# 05-GPS_IMU_SENSORS.net
KiCad netlist of a schematic drawn in Altium Designer
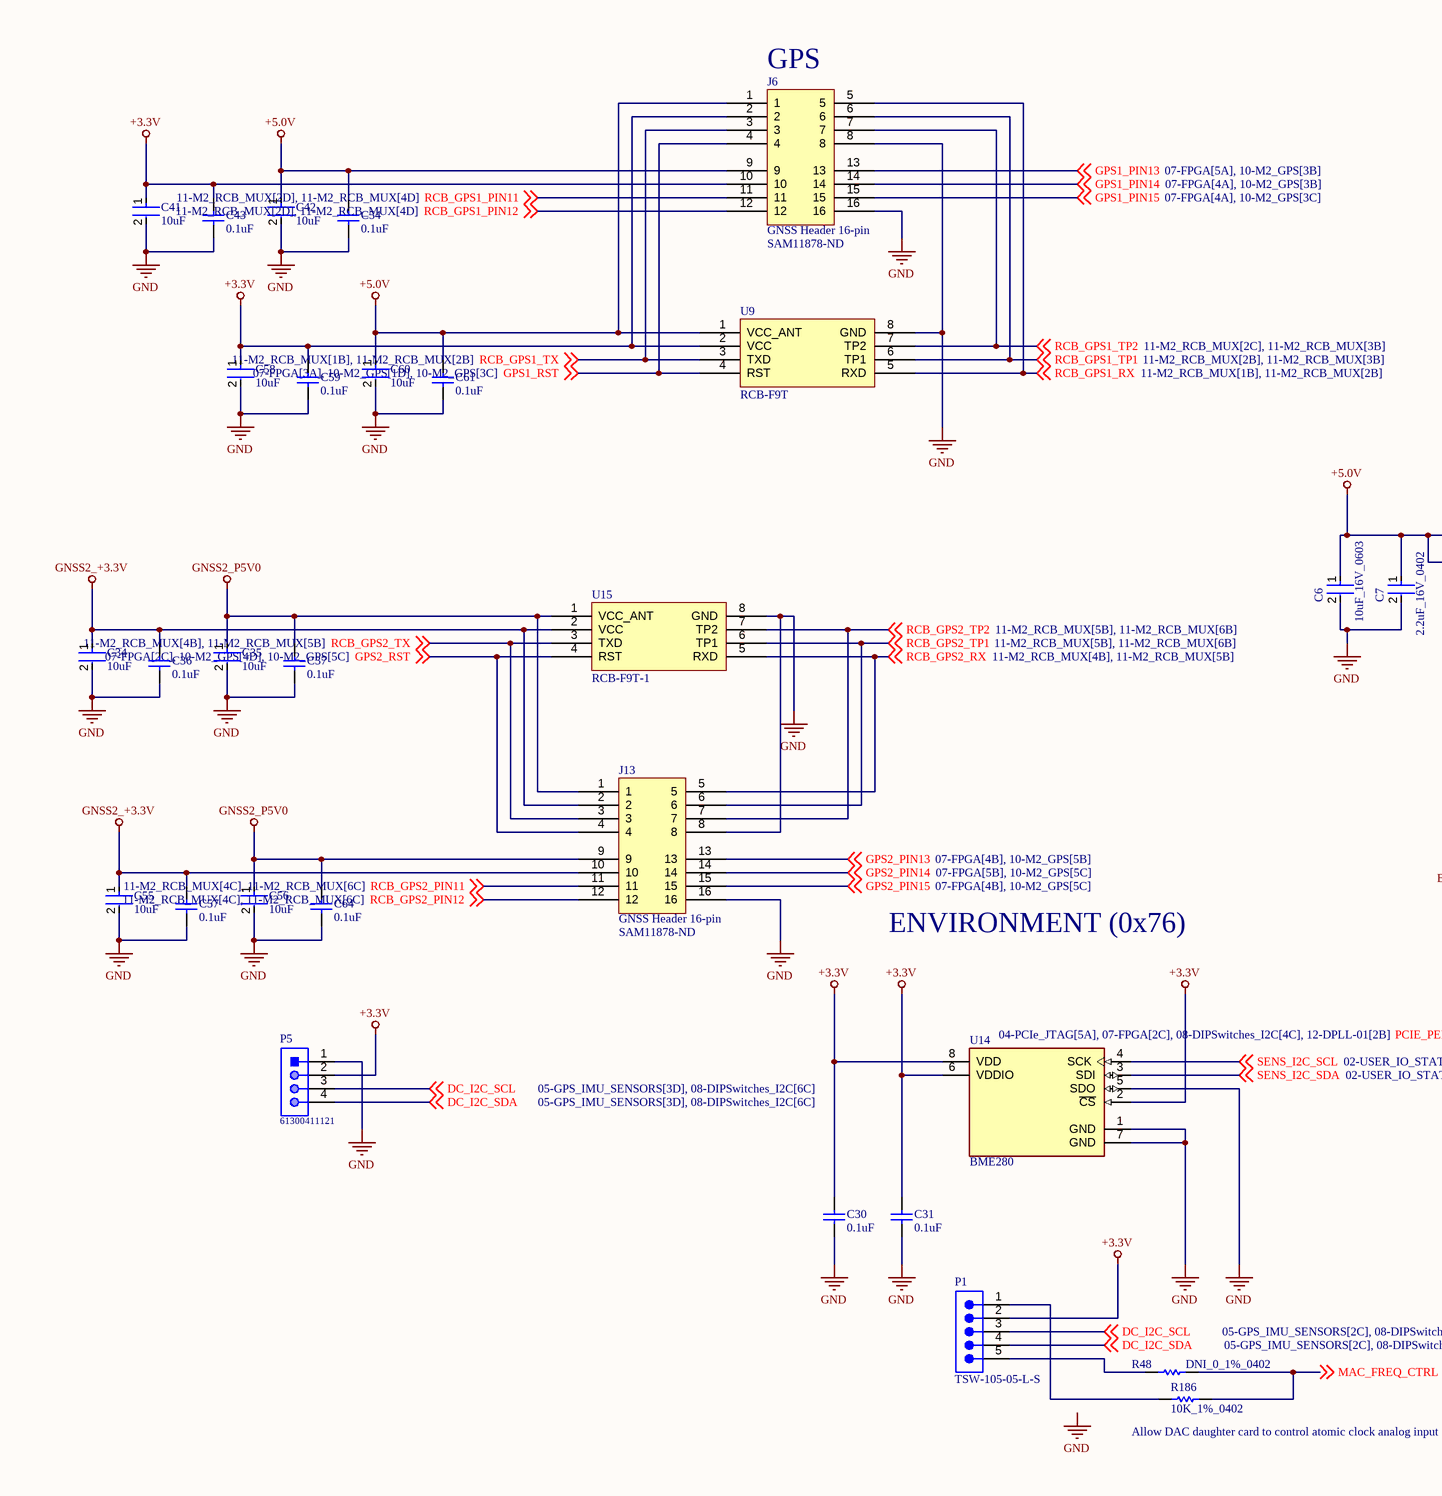
[diagram p0: 05-GPS_IMU_SENSORS.SchDoc, left]
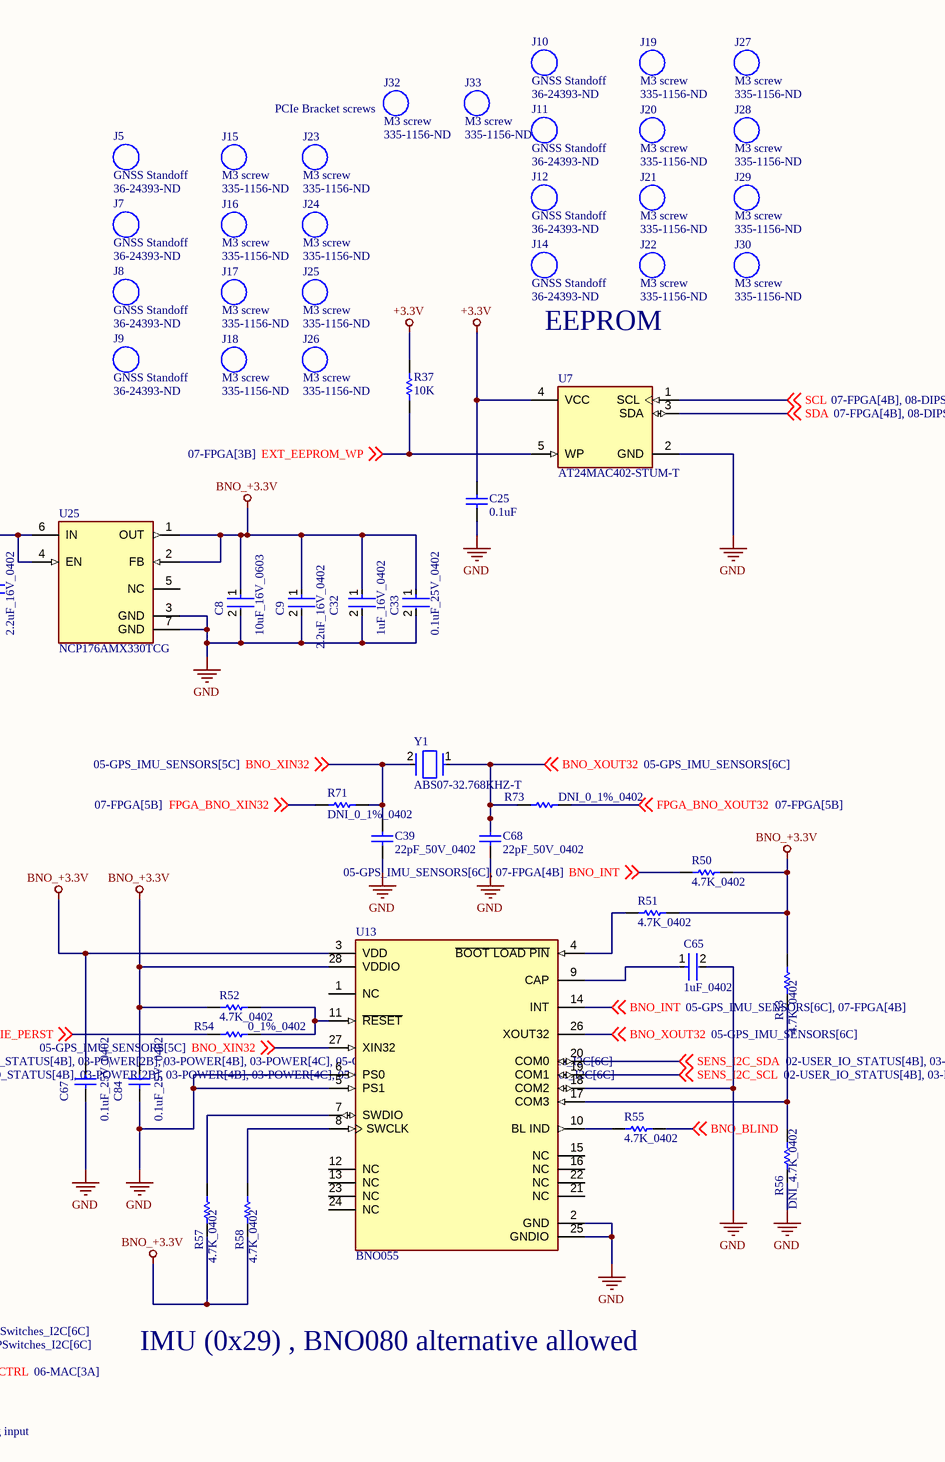
[diagram p1: 05-GPS_IMU_SENSORS.SchDoc, right]

(export (version "E")
  (design (tool "Eeschema 10.0.6"))
  (components
    (comp (ref "C6")
      (value "10uF_16V_0603")
      (footprint "FP-0603-L_1_6_0_2-W_0_8_0-MFG")
      (description "Multilayer Ceramic Capacitor 10uF 16V X5R 20% SMD 0603 T/R")
      (fields (field (name "TOLERANCE") "20%"))
      (libsource (lib "Altium Content Vault") (part "b4654b650e69147ec39a6b967a45e02"))
    )
    (comp (ref "C7")
      (value "2.2uF_16V_0402")
      (footprint "FP-C1005-050-0_05-IPC_A")
      (description "Multilayer Ceramic Capacitors 2.2μF ±10% 16V X5R SMD 0402")
      (fields (field (name "TOLERANCE") "10%"))
      (libsource (lib "Altium Content Vault") (part "b4654b650e69147ec39a6b967a45e02"))
    )
    (comp (ref "C8")
      (value "10uF_16V_0603")
      (footprint "FP-0603-L_1_6_0_2-W_0_8_0-MFG")
      (description "Multilayer Ceramic Capacitor 10uF 16V X5R 20% SMD 0603 T/R")
      (fields (field (name "TOLERANCE") "20%"))
      (libsource (lib "Altium Content Vault") (part "b4654b650e69147ec39a6b967a45e02"))
    )
    (comp (ref "C9")
      (value "2.2uF_16V_0402")
      (footprint "FP-C1005-050-0_05-IPC_A")
      (description "Multilayer Ceramic Capacitors 2.2μF ±10% 16V X5R SMD 0402")
      (fields (field (name "TOLERANCE") "10%"))
      (libsource (lib "Altium Content Vault") (part "b4654b650e69147ec39a6b967a45e02"))
    )
    (comp (ref "C25")
      (value "0.1uF")
      (footprint "CAPC1608X87X45ML20T05")
      (description "C0603X104K5RACAUTO")
      (fields (field (name "MANUFACTURER") "Kemet"))
      (libsource (lib "Altium Content Vault") (part "CAP"))
    )
    (comp (ref "C30")
      (value "0.1uF")
      (footprint "CAPC1608X87X45ML20T05")
      (description "C0603X104K5RACAUTO")
      (fields (field (name "MANUFACTURER") "Kemet"))
      (libsource (lib "Altium Content Vault") (part "CAP"))
    )
    (comp (ref "C31")
      (value "0.1uF")
      (footprint "CAPC1608X87X45ML20T05")
      (description "C0603X104K5RACAUTO")
      (fields (field (name "MANUFACTURER") "Kemet"))
      (libsource (lib "Altium Content Vault") (part "CAP"))
    )
    (comp (ref "C32")
      (value "1uF_16V_0402")
      (footprint "FP-0402-L_1_0_0_05-W_0_5-IPC_A")
      (description "None")
      (fields (field (name "TOLERANCE") "10%"))
      (libsource (lib "Altium Content Vault") (part "b4654b650e69147ec39a6b967a45e02"))
    )
    (comp (ref "C33")
      (value "0.1uF_25V_0402")
      (footprint "FP-0402-L_1_0_1-W_0_5_0_1-IPC_C")
      (description "General Purpose Ceramic Capacitor, 0402, 100nF, 10%, X7R, 15%, 25V")
      (fields (field (name "VOLTAGE") "25V") (field (name "TOLERANCE") "10%"))
      (libsource (lib "Altium Content Vault") (part "b4654b650e69147ec39a6b967a45e02"))
    )
    (comp (ref "C34")
      (value "10uF")
      (footprint "FP-MK212BG-MFG")
      (description "None")
      (fields (field (name "TOLERANCE") "10%") (field (name "VOLTAGE") "16V"))
      (libsource (lib "Altium Content Vault") (part "b4654b650e69147ec39a6b967a45e02"))
    )
    (comp (ref "C35")
      (value "10uF")
      (footprint "FP-MK212BG-MFG")
      (description "None")
      (fields (field (name "TOLERANCE") "10%") (field (name "VOLTAGE") "16V"))
      (libsource (lib "Altium Content Vault") (part "b4654b650e69147ec39a6b967a45e02"))
    )
    (comp (ref "C36")
      (value "0.1uF")
      (footprint "CAPC1608X87X45ML20T05")
      (description "C0603X104K5RACAUTO")
      (fields (field (name "MANUFACTURER") "Kemet"))
      (libsource (lib "Altium Content Vault") (part "CAP"))
    )
    (comp (ref "C37")
      (value "0.1uF")
      (footprint "CAPC1608X87X45ML20T05")
      (description "C0603X104K5RACAUTO")
      (fields (field (name "MANUFACTURER") "Kemet"))
      (libsource (lib "Altium Content Vault") (part "CAP"))
    )
    (comp (ref "C39")
      (value "22pF_50V_0402")
      (footprint "CAPC1005X55X25ML05T05")
      (description "Chip Capacitor, 22 pF, +/- 5%, 50 V, -55 to 125 degC, 0402 (1005 Metric), RoHS, Tape and Reel")
      (fields (field (name "MANUFACTURER") "Yageo") (field (name "TOLERANCE") "5%"))
      (libsource (lib "Altium Content Vault") (part "CAP-NP-2"))
    )
    (comp (ref "C41")
      (value "10uF")
      (footprint "FP-MK212BG-MFG")
      (description "None")
      (fields (field (name "TOLERANCE") "10%") (field (name "VOLTAGE") "16V"))
      (libsource (lib "Altium Content Vault") (part "b4654b650e69147ec39a6b967a45e02"))
    )
    (comp (ref "C42")
      (value "10uF")
      (footprint "FP-MK212BG-MFG")
      (description "None")
      (fields (field (name "TOLERANCE") "10%") (field (name "VOLTAGE") "16V"))
      (libsource (lib "Altium Content Vault") (part "b4654b650e69147ec39a6b967a45e02"))
    )
    (comp (ref "C43")
      (value "0.1uF")
      (footprint "CAPC1608X87X45ML20T05")
      (description "C0603X104K5RACAUTO")
      (fields (field (name "MANUFACTURER") "Kemet"))
      (libsource (lib "Altium Content Vault") (part "CAP"))
    )
    (comp (ref "C54")
      (value "0.1uF")
      (footprint "CAPC1608X87X45ML20T05")
      (description "C0603X104K5RACAUTO")
      (fields (field (name "MANUFACTURER") "Kemet"))
      (libsource (lib "Altium Content Vault") (part "CAP"))
    )
    (comp (ref "C55")
      (value "10uF")
      (footprint "FP-MK212BG-MFG")
      (description "None")
      (fields (field (name "TOLERANCE") "10%") (field (name "VOLTAGE") "16V"))
      (libsource (lib "Altium Content Vault") (part "b4654b650e69147ec39a6b967a45e02"))
    )
    (comp (ref "C56")
      (value "10uF")
      (footprint "FP-MK212BG-MFG")
      (description "None")
      (fields (field (name "TOLERANCE") "10%") (field (name "VOLTAGE") "16V"))
      (libsource (lib "Altium Content Vault") (part "b4654b650e69147ec39a6b967a45e02"))
    )
    (comp (ref "C57")
      (value "0.1uF")
      (footprint "CAPC1608X87X45ML20T05")
      (description "C0603X104K5RACAUTO")
      (fields (field (name "MANUFACTURER") "Kemet"))
      (libsource (lib "Altium Content Vault") (part "CAP"))
    )
    (comp (ref "C58")
      (value "10uF")
      (footprint "FP-MK212BG-MFG")
      (description "None")
      (fields (field (name "TOLERANCE") "10%") (field (name "VOLTAGE") "16V"))
      (libsource (lib "Altium Content Vault") (part "b4654b650e69147ec39a6b967a45e02"))
    )
    (comp (ref "C59")
      (value "0.1uF")
      (footprint "CAPC1608X87X45ML20T05")
      (description "C0603X104K5RACAUTO")
      (fields (field (name "MANUFACTURER") "Kemet"))
      (libsource (lib "Altium Content Vault") (part "CAP"))
    )
    (comp (ref "C60")
      (value "10uF")
      (footprint "FP-MK212BG-MFG")
      (description "None")
      (fields (field (name "TOLERANCE") "10%") (field (name "VOLTAGE") "16V"))
      (libsource (lib "Altium Content Vault") (part "b4654b650e69147ec39a6b967a45e02"))
    )
    (comp (ref "C61")
      (value "0.1uF")
      (footprint "CAPC1608X87X45ML20T05")
      (description "C0603X104K5RACAUTO")
      (fields (field (name "MANUFACTURER") "Kemet"))
      (libsource (lib "Altium Content Vault") (part "CAP"))
    )
    (comp (ref "C64")
      (value "0.1uF")
      (footprint "CAPC1608X87X45ML20T05")
      (description "C0603X104K5RACAUTO")
      (fields (field (name "MANUFACTURER") "Kemet"))
      (libsource (lib "Altium Content Vault") (part "CAP"))
    )
    (comp (ref "C65")
      (value "1uF_0402")
      (footprint "FP-0402-L_1_0_0_05-W_0_5-IPC_C")
      (description "None")
      (fields (field (name "TOLERANCE") "20%") (field (name "VOLTAGE") "16V"))
      (libsource (lib "Altium Content Vault") (part "b4654b650e69147ec39a6b967a45e02"))
    )
    (comp (ref "C67")
      (value "0.1uF_25V_0402")
      (footprint "CAPC1005X56X25NL10T15")
      (fields
        (field (name "PART NUMBER") "04023D104KAT2A")
        (field (name "MANUFACTURER") "AVX Interconnect / Elco")
      )
      (libsource (lib "Altium Content Vault") (part "CAP"))
    )
    (comp (ref "C68")
      (value "22pF_50V_0402")
      (footprint "CAPC1005X55X25ML05T05")
      (description "Chip Capacitor, 22 pF, +/- 5%, 50 V, -55 to 125 degC, 0402 (1005 Metric), RoHS, Tape and Reel")
      (fields (field (name "MANUFACTURER") "Yageo") (field (name "TOLERANCE") "5%"))
      (libsource (lib "Altium Content Vault") (part "CAP-NP-2"))
    )
    (comp (ref "C84")
      (value "0.1uF_25V_0402")
      (footprint "CAPC1005X56X25NL10T15")
      (fields
        (field (name "PART NUMBER") "04023D104KAT2A")
        (field (name "MANUFACTURER") "AVX Interconnect / Elco")
      )
      (libsource (lib "Altium Content Vault") (part "CAP"))
    )
    (comp (ref "J5")
      (value "GNSS Standoff")
      (fields (field (name "SUPPLIER PART NUMBER 1") "36-24393-ND"))
      (libsource (lib "FPGA_CONN") (part "GNSS Standoff"))
    )
    (comp (ref "J6")
      (value "GNSS Header 16-pin")
      (footprint "GNSS Header 16-pin")
      (fields (field (name "SUPPLIER PART NUMBER 1") "SAM11878-ND"))
      (libsource (lib "FPGA_CONN") (part "GNSS Header 16-pin"))
    )
    (comp (ref "J7")
      (value "GNSS Standoff")
      (fields (field (name "SUPPLIER PART NUMBER 1") "36-24393-ND"))
      (libsource (lib "FPGA_CONN") (part "GNSS Standoff"))
    )
    (comp (ref "J8")
      (value "GNSS Standoff")
      (fields (field (name "SUPPLIER PART NUMBER 1") "36-24393-ND"))
      (libsource (lib "FPGA_CONN") (part "GNSS Standoff"))
    )
    (comp (ref "J9")
      (value "GNSS Standoff")
      (fields (field (name "SUPPLIER PART NUMBER 1") "36-24393-ND"))
      (libsource (lib "FPGA_CONN") (part "GNSS Standoff"))
    )
    (comp (ref "J10")
      (value "GNSS Standoff")
      (fields (field (name "SUPPLIER PART NUMBER 1") "36-24393-ND"))
      (libsource (lib "FPGA_CONN") (part "GNSS Standoff"))
    )
    (comp (ref "J11")
      (value "GNSS Standoff")
      (fields (field (name "SUPPLIER PART NUMBER 1") "36-24393-ND"))
      (libsource (lib "FPGA_CONN") (part "GNSS Standoff"))
    )
    (comp (ref "J12")
      (value "GNSS Standoff")
      (fields (field (name "SUPPLIER PART NUMBER 1") "36-24393-ND"))
      (libsource (lib "FPGA_CONN") (part "GNSS Standoff"))
    )
    (comp (ref "J13")
      (value "GNSS Header 16-pin")
      (footprint "GNSS Header 16-pin")
      (fields (field (name "SUPPLIER PART NUMBER 1") "SAM11878-ND"))
      (libsource (lib "FPGA_CONN") (part "GNSS Header 16-pin"))
    )
    (comp (ref "J14")
      (value "GNSS Standoff")
      (fields (field (name "SUPPLIER PART NUMBER 1") "36-24393-ND"))
      (libsource (lib "FPGA_CONN") (part "GNSS Standoff"))
    )
    (comp (ref "J15")
      (value "M3 screw")
      (fields (field (name "SUPPLIER PART NUMBER 1") "335-1156-ND"))
      (libsource (lib "FPGA_CONN") (part "M3 screw"))
    )
    (comp (ref "J16")
      (value "M3 screw")
      (fields (field (name "SUPPLIER PART NUMBER 1") "335-1156-ND"))
      (libsource (lib "FPGA_CONN") (part "M3 screw"))
    )
    (comp (ref "J17")
      (value "M3 screw")
      (fields (field (name "SUPPLIER PART NUMBER 1") "335-1156-ND"))
      (libsource (lib "FPGA_CONN") (part "M3 screw"))
    )
    (comp (ref "J18")
      (value "M3 screw")
      (fields (field (name "SUPPLIER PART NUMBER 1") "335-1156-ND"))
      (libsource (lib "FPGA_CONN") (part "M3 screw"))
    )
    (comp (ref "J19")
      (value "M3 screw")
      (fields (field (name "SUPPLIER PART NUMBER 1") "335-1156-ND"))
      (libsource (lib "FPGA_CONN") (part "M3 screw"))
    )
    (comp (ref "J20")
      (value "M3 screw")
      (fields (field (name "SUPPLIER PART NUMBER 1") "335-1156-ND"))
      (libsource (lib "FPGA_CONN") (part "M3 screw"))
    )
    (comp (ref "J21")
      (value "M3 screw")
      (fields (field (name "SUPPLIER PART NUMBER 1") "335-1156-ND"))
      (libsource (lib "FPGA_CONN") (part "M3 screw"))
    )
    (comp (ref "J22")
      (value "M3 screw")
      (fields (field (name "SUPPLIER PART NUMBER 1") "335-1156-ND"))
      (libsource (lib "FPGA_CONN") (part "M3 screw"))
    )
    (comp (ref "J23")
      (value "M3 screw")
      (fields (field (name "SUPPLIER PART NUMBER 1") "335-1156-ND"))
      (libsource (lib "FPGA_CONN") (part "M3 screw"))
    )
    (comp (ref "J24")
      (value "M3 screw")
      (fields (field (name "SUPPLIER PART NUMBER 1") "335-1156-ND"))
      (libsource (lib "FPGA_CONN") (part "M3 screw"))
    )
    (comp (ref "J25")
      (value "M3 screw")
      (fields (field (name "SUPPLIER PART NUMBER 1") "335-1156-ND"))
      (libsource (lib "FPGA_CONN") (part "M3 screw"))
    )
    (comp (ref "J26")
      (value "M3 screw")
      (fields (field (name "SUPPLIER PART NUMBER 1") "335-1156-ND"))
      (libsource (lib "FPGA_CONN") (part "M3 screw"))
    )
    (comp (ref "J27")
      (value "M3 screw")
      (fields (field (name "SUPPLIER PART NUMBER 1") "335-1156-ND"))
      (libsource (lib "FPGA_CONN") (part "M3 screw"))
    )
    (comp (ref "J28")
      (value "M3 screw")
      (fields (field (name "SUPPLIER PART NUMBER 1") "335-1156-ND"))
      (libsource (lib "FPGA_CONN") (part "M3 screw"))
    )
    (comp (ref "J29")
      (value "M3 screw")
      (fields (field (name "SUPPLIER PART NUMBER 1") "335-1156-ND"))
      (libsource (lib "FPGA_CONN") (part "M3 screw"))
    )
    (comp (ref "J30")
      (value "M3 screw")
      (fields (field (name "SUPPLIER PART NUMBER 1") "335-1156-ND"))
      (libsource (lib "FPGA_CONN") (part "M3 screw"))
    )
    (comp (ref "J32")
      (value "M3 screw")
      (fields (field (name "SUPPLIER PART NUMBER 1") "335-1156-ND"))
      (libsource (lib "FPGA_CONN") (part "M3 screw"))
    )
    (comp (ref "J33")
      (value "M3 screw")
      (fields (field (name "SUPPLIER PART NUMBER 1") "335-1156-ND"))
      (libsource (lib "FPGA_CONN") (part "M3 screw"))
    )
    (comp (ref "P1")
      (value "TSW-105-05-L-S")
      (footprint "SMTC-TSW-105-05-X-S")
      (description "0.025\" SQ Post Header, Through-hole, Vertical, -55 to 125 degC, 2.54 mm Pitch, 5-Pin, Male, RoHS")
      (fields (field (name "MANUFACTURER") "Samtec"))
      (libsource (lib "Altium Content Vault") (part "SMTC-TSW-105-05-X-S"))
    )
    (comp (ref "P5")
      (value "61300411121")
      (footprint "61300411121")
      (description "THT Vertical Pin Header WR-PHD, Pitch 2.54 mm, Single Row, 4 pins")
      (fields (field (name "MANUFACTURER") "Wurth Elektronik") (field (name "PUBLISHER") "WurthElektronik"))
      (libsource (lib "Altium Content Vault") (part "WE-CN-1P-M-R4"))
    )
    (comp (ref "R37")
      (value "10K")
      (footprint "RESC1608X55X30LL15T20")
      (fields (field (name "TOLERANCE") "±1%") (field (name "MANUFACTURER") "Stackpole-Electronics-Inc."))
      (libsource (lib "Altium Content Vault") (part "RES-2"))
    )
    (comp (ref "R48")
      (value "DNI_0_1%_0402")
      (footprint "RESC1005X40X25LL05T05")
      (description "Chip Resistor, 0 Ohm, 0.1 W, -55 to 155 degC, 0402 (1005 Metric), RoHS, Tape and Reel")
      (fields (field (name "MANUFACTURER") "Panasonic") (field (name "TOLERANCE") "5%"))
      (libsource (lib "Altium Content Vault") (part "RES-2"))
    )
    (comp (ref "R50")
      (value "4.7K_0402")
      (footprint "RESC1005X40X25LL05T05")
      (description "Chip Resistor, 4.7 KOhm, +/- 1%, 0.1 W, -55 to 155 degC, 0402 (1005 Metric), RoHS, Tape and Reel")
      (fields (field (name "TOLERANCE") "1%") (field (name "PARTNUMBER") "ERJ-2RKF4701X"))
      (libsource (lib "Altium Content Vault") (part "RES-2"))
    )
    (comp (ref "R51")
      (value "4.7K_0402")
      (footprint "RESC1005X40X25LL05T05")
      (description "Chip Resistor, 4.7 KOhm, +/- 1%, 0.1 W, -55 to 155 degC, 0402 (1005 Metric), RoHS, Tape and Reel")
      (fields (field (name "TOLERANCE") "1%") (field (name "PARTNUMBER") "ERJ-2RKF4701X"))
      (libsource (lib "Altium Content Vault") (part "RES-2"))
    )
    (comp (ref "R52")
      (value "4.7K_0402")
      (footprint "RESC1005X40X25LL05T05")
      (description "Chip Resistor, 4.7 KOhm, +/- 1%, 0.1 W, -55 to 155 degC, 0402 (1005 Metric), RoHS, Tape and Reel")
      (fields (field (name "TOLERANCE") "1%") (field (name "PARTNUMBER") "ERJ-2RKF4701X"))
      (libsource (lib "Altium Content Vault") (part "RES-2"))
    )
    (comp (ref "R53")
      (value "4.7K_0402")
      (footprint "RESC1005X40X25LL05T05")
      (description "Chip Resistor, 4.7 KOhm, +/- 1%, 0.1 W, -55 to 155 degC, 0402 (1005 Metric), RoHS, Tape and Reel")
      (fields (field (name "TOLERANCE") "1%") (field (name "PARTNUMBER") "ERJ-2RKF4701X"))
      (libsource (lib "Altium Content Vault") (part "RES-2"))
    )
    (comp (ref "R54")
      (value "0_1%_0402")
      (footprint "RESC1005X40X25LL05T05")
      (description "Chip Resistor, 0 Ohm, 0.1 W, -55 to 155 degC, 0402 (1005 Metric), RoHS, Tape and Reel")
      (fields (field (name "MANUFACTURER") "Panasonic") (field (name "TOLERANCE") "5%"))
      (libsource (lib "Altium Content Vault") (part "RES-2"))
    )
    (comp (ref "R55")
      (value "4.7K_0402")
      (footprint "RESC1005X40X25LL05T05")
      (description "Chip Resistor, 4.7 KOhm, +/- 1%, 0.1 W, -55 to 155 degC, 0402 (1005 Metric), RoHS, Tape and Reel")
      (fields (field (name "TOLERANCE") "1%") (field (name "PARTNUMBER") "ERJ-2RKF4701X"))
      (libsource (lib "Altium Content Vault") (part "RES-2"))
    )
    (comp (ref "R56")
      (value "DNI_4.7K_0402")
      (footprint "RESC1005X40X25LL05T05")
      (description "Chip Resistor, 4.7 KOhm, +/- 1%, 0.1 W, -55 to 155 degC, 0402 (1005 Metric), RoHS, Tape and Reel")
      (fields (field (name "TOLERANCE") "1%") (field (name "PARTNUMBER") "ERJ-2RKF4701X"))
      (libsource (lib "Altium Content Vault") (part "RES-2"))
    )
    (comp (ref "R57")
      (value "4.7K_0402")
      (footprint "RESC1005X40X25LL05T05")
      (description "Chip Resistor, 4.7 KOhm, +/- 1%, 0.1 W, -55 to 155 degC, 0402 (1005 Metric), RoHS, Tape and Reel")
      (fields (field (name "TOLERANCE") "1%") (field (name "PARTNUMBER") "ERJ-2RKF4701X"))
      (libsource (lib "Altium Content Vault") (part "RES-2"))
    )
    (comp (ref "R58")
      (value "4.7K_0402")
      (footprint "RESC1005X40X25LL05T05")
      (description "Chip Resistor, 4.7 KOhm, +/- 1%, 0.1 W, -55 to 155 degC, 0402 (1005 Metric), RoHS, Tape and Reel")
      (fields (field (name "TOLERANCE") "1%") (field (name "PARTNUMBER") "ERJ-2RKF4701X"))
      (libsource (lib "Altium Content Vault") (part "RES-2"))
    )
    (comp (ref "R71")
      (value "DNI_0_1%_0402")
      (footprint "RESC1005X40X25LL05T05")
      (description "Chip Resistor, 0 Ohm, 0.1 W, -55 to 155 degC, 0402 (1005 Metric), RoHS, Tape and Reel")
      (fields (field (name "MANUFACTURER") "Panasonic") (field (name "TOLERANCE") "5%"))
      (libsource (lib "Altium Content Vault") (part "RES-2"))
    )
    (comp (ref "R73")
      (value "DNI_0_1%_0402")
      (footprint "RESC1005X40X25LL05T05")
      (description "Chip Resistor, 0 Ohm, 0.1 W, -55 to 155 degC, 0402 (1005 Metric), RoHS, Tape and Reel")
      (fields (field (name "MANUFACTURER") "Panasonic") (field (name "TOLERANCE") "5%"))
      (libsource (lib "Altium Content Vault") (part "RES-2"))
    )
    (comp (ref "R186")
      (value "10K_1%_0402")
      (footprint "RESC1005X40X25LL05T10")
      (fields (field (name "PART NUMBER") "RC0402FR-0710KL") (field (name "MANUFACTURER") "Yageo / Phycomp"))
      (libsource (lib "Altium Content Vault") (part "RES"))
    )
    (comp (ref "U7")
      (value "AT24MAC402-STUM-T")
      (footprint "FP-5TS1-IPC_C")
      (description "IC EEPROM 2K I2C 1MHZ SOT23-5")
      (fields
        (field (name "MANUFACTURER") "Microchip")
        (field (name "OCTOPART") "https://octopart.com/at24mac402-stum-t-microchip-77758112")
      )
      (libsource (lib "Altium Content Vault") (part "93fe34f5f049140596bab6421a6454b"))
    )
    (comp (ref "U9")
      (value "RCB-F9T")
      (footprint "GNSS")
      (description "MOD, GPS")
      (fields (field (name "VELENTIUM PART NUM") "<V PART NUM>"))
      (libsource (lib "Modules") (part "RCB-F9T"))
    )
    (comp (ref "U13")
      (value "BNO055")
      (footprint "FP-BNO055-MFG")
      (description "IMU ACCEL/GYRO/MAG I2C 28LGA")
      (libsource (lib "Altium Content Vault") (part "ba837af00a0b6167256f888b31462b1"))
    )
    (comp (ref "U14")
      (value "BME280")
      (footprint "FP-BME280-MFG")
      (description "SENSOR PRESSURE HUMIDITY TEMP")
      (libsource (lib "Altium Content Vault") (part "d58e2f6669bc67e6a2bc6a28610ca79"))
    )
    (comp (ref "U15")
      (value "RCB-F9T-1")
      (footprint "GNSS")
      (description "MOD, GPS")
      (fields (field (name "VELENTIUM PART NUM") "<V PART NUM>"))
      (libsource (lib "Modules") (part "RCB-F9T"))
    )
    (comp (ref "U25")
      (value "NCP176AMX330TCG")
      (footprint "FP-711AT-MFG")
      (description "IC REG LINEAR 3.3V 500MA 6XDFN")
      (fields
        (field (name "MANUFACTURER") "ON Semiconductor")
        (field (name "OCTOPART") "https://octopart.com/ncp176amx330tcg-on+semiconductor-61522616")
      )
      (libsource (lib "Altium Content Vault") (part "a38d0f79c2a9f01c07a7e52882ed186"))
    )
    (comp (ref "Y1")
      (value "ABS07-32.768KHZ-T")
      (footprint "FP-ABS07-MFG")
      (description "Crystal 32.768kHz ±20ppm (Tol) 12.5pF FUND 70kΩ 2-Pin CSMD T/R")
      (fields (field (name "TOLERANCE") "20ppm"))
      (libsource (lib "Altium Content Vault") (part "c23a69dc6c9e2f18f2079038eb95dd1"))
    )
  )
  (nets
    (net (code "1") (name "+3.3V") (class "Default")
      (node (ref "C25") (pin "2") (pinfunction "2_2") (pintype "passive"))
      (node (ref "C30") (pin "2") (pinfunction "2_2") (pintype "passive"))
      (node (ref "C31") (pin "2") (pinfunction "2_2") (pintype "passive"))
      (node (ref "C41") (pin "1") (pinfunction "1_1") (pintype "passive"))
      (node (ref "C43") (pin "2") (pinfunction "2_2") (pintype "passive"))
      (node (ref "C58") (pin "1") (pinfunction "1_1") (pintype "passive"))
      (node (ref "C59") (pin "2") (pinfunction "2_2") (pintype "passive"))
      (node (ref "J6") (pin "10") (pinfunction "10_10") (pintype "passive"))
      (node (ref "J6") (pin "2") (pinfunction "2_2") (pintype "passive"))
      (node (ref "P1") (pin "2") (pinfunction "2_2") (pintype "passive"))
      (node (ref "P5") (pin "2") (pinfunction "2_2") (pintype "passive"))
      (node (ref "R37") (pin "2") (pinfunction "2_2") (pintype "passive"))
      (node (ref "U14") (pin "2") (pinfunction "~{CS}_2") (pintype "input"))
      (node (ref "U14") (pin "6") (pinfunction "VDDIO_6") (pintype "power_in"))
      (node (ref "U14") (pin "8") (pinfunction "VDD_8") (pintype "power_in"))
      (node (ref "U7") (pin "4") (pinfunction "VCC_4") (pintype "power_in"))
      (node (ref "U9") (pin "2") (pinfunction "VCC_2") (pintype "passive"))
    )
    (net (code "2") (name "+5.0V") (class "Default")
      (node (ref "C42") (pin "1") (pinfunction "1_1") (pintype "passive"))
      (node (ref "C54") (pin "2") (pinfunction "2_2") (pintype "passive"))
      (node (ref "C6") (pin "1") (pinfunction "1_1") (pintype "passive"))
      (node (ref "C60") (pin "1") (pinfunction "1_1") (pintype "passive"))
      (node (ref "C61") (pin "2") (pinfunction "2_2") (pintype "passive"))
      (node (ref "C7") (pin "1") (pinfunction "1_1") (pintype "passive"))
      (node (ref "J6") (pin "1") (pinfunction "1_1") (pintype "passive"))
      (node (ref "J6") (pin "9") (pinfunction "9_9") (pintype "passive"))
      (node (ref "U25") (pin "4") (pinfunction "EN_4") (pintype "input"))
      (node (ref "U25") (pin "6") (pinfunction "IN_6") (pintype "power_in"))
      (node (ref "U9") (pin "1") (pinfunction "VCC_ANT_1") (pintype "passive"))
    )
    (net (code "3") (name "BNO_+3.3V") (class "Default")
      (node (ref "C32") (pin "1") (pinfunction "1_1") (pintype "passive"))
      (node (ref "C33") (pin "1") (pinfunction "1_1") (pintype "passive"))
      (node (ref "C67") (pin "2") (pinfunction "2_2") (pintype "passive"))
      (node (ref "C8") (pin "1") (pinfunction "1_1") (pintype "passive"))
      (node (ref "C84") (pin "2") (pinfunction "2_2") (pintype "passive"))
      (node (ref "C9") (pin "1") (pinfunction "1_1") (pintype "passive"))
      (node (ref "R50") (pin "1") (pinfunction "1_1") (pintype "passive"))
      (node (ref "R51") (pin "1") (pinfunction "1_1") (pintype "passive"))
      (node (ref "R52") (pin "2") (pinfunction "2_2") (pintype "passive"))
      (node (ref "R53") (pin "2") (pinfunction "2_2") (pintype "passive"))
      (node (ref "R57") (pin "1") (pinfunction "1_1") (pintype "passive"))
      (node (ref "R58") (pin "1") (pinfunction "1_1") (pintype "passive"))
      (node (ref "U13") (pin "28") (pinfunction "VDDIO_28") (pintype "power_in"))
      (node (ref "U13") (pin "3") (pinfunction "VDD_3") (pintype "power_in"))
      (node (ref "U25") (pin "1") (pinfunction "OUT_1") (pintype "output"))
      (node (ref "U25") (pin "2") (pinfunction "FB_2") (pintype "input"))
    )
    (net (code "4") (name "BNO_BLIND") (class "Default")
      (node (ref "R55") (pin "1") (pinfunction "1_1") (pintype "passive"))
    )
    (net (code "5") (name "BNO_INT") (class "Default")
      (node (ref "R50") (pin "2") (pinfunction "2_2") (pintype "passive"))
      (node (ref "U13") (pin "14") (pinfunction "INT_14") (pintype "passive"))
    )
    (net (code "6") (name "BNO_XIN32") (class "Default")
      (node (ref "C39") (pin "2") (pinfunction "2_2") (pintype "passive"))
      (node (ref "R71") (pin "1") (pinfunction "1_1") (pintype "passive"))
      (node (ref "U13") (pin "27") (pinfunction "XIN32_27") (pintype "input"))
      (node (ref "Y1") (pin "2") (pinfunction "2_2") (pintype "passive"))
    )
    (net (code "7") (name "BNO_XOUT32") (class "Default")
      (node (ref "C68") (pin "2") (pinfunction "2_2") (pintype "passive"))
      (node (ref "R73") (pin "1") (pinfunction "1_1") (pintype "passive"))
      (node (ref "U13") (pin "26") (pinfunction "XOUT32_26") (pintype "passive"))
      (node (ref "Y1") (pin "1") (pinfunction "1_1") (pintype "passive"))
    )
    (net (code "8") (name "DC_I2C_SCL") (class "Default")
      (node (ref "P1") (pin "3") (pinfunction "3_3") (pintype "passive"))
      (node (ref "P5") (pin "3") (pinfunction "3_3") (pintype "passive"))
    )
    (net (code "9") (name "DC_I2C_SDA") (class "Default")
      (node (ref "P1") (pin "4") (pinfunction "4_4") (pintype "passive"))
      (node (ref "P5") (pin "4") (pinfunction "4_4") (pintype "passive"))
    )
    (net (code "10") (name "EXT_EEPROM_WP") (class "Default")
      (node (ref "R37") (pin "1") (pinfunction "1_1") (pintype "passive"))
      (node (ref "U7") (pin "5") (pinfunction "WP_5") (pintype "input"))
    )
    (net (code "11") (name "FPGA_BNO_XIN32") (class "Default")
      (node (ref "R71") (pin "2") (pinfunction "2_2") (pintype "passive"))
    )
    (net (code "12") (name "FPGA_BNO_XOUT32") (class "Default")
      (node (ref "R73") (pin "2") (pinfunction "2_2") (pintype "passive"))
    )
    (net (code "13") (name "GND") (class "Default")
      (node (ref "C25") (pin "1") (pinfunction "1_1") (pintype "passive"))
      (node (ref "C30") (pin "1") (pinfunction "1_1") (pintype "passive"))
      (node (ref "C31") (pin "1") (pinfunction "1_1") (pintype "passive"))
      (node (ref "C32") (pin "2") (pinfunction "2_2") (pintype "passive"))
      (node (ref "C33") (pin "2") (pinfunction "2_2") (pintype "passive"))
      (node (ref "C34") (pin "2") (pinfunction "2_2") (pintype "passive"))
      (node (ref "C35") (pin "2") (pinfunction "2_2") (pintype "passive"))
      (node (ref "C36") (pin "1") (pinfunction "1_1") (pintype "passive"))
      (node (ref "C37") (pin "1") (pinfunction "1_1") (pintype "passive"))
      (node (ref "C39") (pin "1") (pinfunction "1_1") (pintype "passive"))
      (node (ref "C41") (pin "2") (pinfunction "2_2") (pintype "passive"))
      (node (ref "C42") (pin "2") (pinfunction "2_2") (pintype "passive"))
      (node (ref "C43") (pin "1") (pinfunction "1_1") (pintype "passive"))
      (node (ref "C54") (pin "1") (pinfunction "1_1") (pintype "passive"))
      (node (ref "C55") (pin "2") (pinfunction "2_2") (pintype "passive"))
      (node (ref "C56") (pin "2") (pinfunction "2_2") (pintype "passive"))
      (node (ref "C57") (pin "1") (pinfunction "1_1") (pintype "passive"))
      (node (ref "C58") (pin "2") (pinfunction "2_2") (pintype "passive"))
      (node (ref "C59") (pin "1") (pinfunction "1_1") (pintype "passive"))
      (node (ref "C6") (pin "2") (pinfunction "2_2") (pintype "passive"))
      (node (ref "C60") (pin "2") (pinfunction "2_2") (pintype "passive"))
      (node (ref "C61") (pin "1") (pinfunction "1_1") (pintype "passive"))
      (node (ref "C64") (pin "1") (pinfunction "1_1") (pintype "passive"))
      (node (ref "C65") (pin "2") (pinfunction "2_2") (pintype "passive"))
      (node (ref "C67") (pin "1") (pinfunction "1_1") (pintype "passive"))
      (node (ref "C68") (pin "1") (pinfunction "1_1") (pintype "passive"))
      (node (ref "C7") (pin "2") (pinfunction "2_2") (pintype "passive"))
      (node (ref "C8") (pin "2") (pinfunction "2_2") (pintype "passive"))
      (node (ref "C84") (pin "1") (pinfunction "1_1") (pintype "passive"))
      (node (ref "C9") (pin "2") (pinfunction "2_2") (pintype "passive"))
      (node (ref "J13") (pin "16") (pinfunction "16_16") (pintype "passive"))
      (node (ref "J13") (pin "8") (pinfunction "8_8") (pintype "passive"))
      (node (ref "J6") (pin "16") (pinfunction "16_16") (pintype "passive"))
      (node (ref "J6") (pin "8") (pinfunction "8_8") (pintype "passive"))
      (node (ref "P5") (pin "1") (pinfunction "1_1") (pintype "passive"))
      (node (ref "R56") (pin "1") (pinfunction "1_1") (pintype "passive"))
      (node (ref "U13") (pin "18") (pinfunction "COM2_18") (pintype "bidirectional"))
      (node (ref "U13") (pin "2") (pinfunction "GND_2") (pintype "power_in"))
      (node (ref "U13") (pin "25") (pinfunction "GNDIO_25") (pintype "power_in"))
      (node (ref "U13") (pin "5") (pinfunction "PS1_5") (pintype "input"))
      (node (ref "U13") (pin "6") (pinfunction "PS0_6") (pintype "input"))
      (node (ref "U14") (pin "1") (pinfunction "GND_1") (pintype "power_in"))
      (node (ref "U14") (pin "5") (pinfunction "SDO_5") (pintype "bidirectional"))
      (node (ref "U14") (pin "7") (pinfunction "GND_7") (pintype "power_in"))
      (node (ref "U15") (pin "8") (pinfunction "GND_8") (pintype "passive"))
      (node (ref "U25") (pin "3") (pinfunction "GND_3") (pintype "power_in"))
      (node (ref "U25") (pin "7") (pinfunction "GND_7") (pintype "power_in"))
      (node (ref "U7") (pin "2") (pinfunction "GND_2") (pintype "power_in"))
      (node (ref "U9") (pin "8") (pinfunction "GND_8") (pintype "passive"))
    )
    (net (code "14") (name "GNSS2_+3.3V") (class "Default")
      (node (ref "C34") (pin "1") (pinfunction "1_1") (pintype "passive"))
      (node (ref "C36") (pin "2") (pinfunction "2_2") (pintype "passive"))
      (node (ref "C55") (pin "1") (pinfunction "1_1") (pintype "passive"))
      (node (ref "C57") (pin "2") (pinfunction "2_2") (pintype "passive"))
      (node (ref "J13") (pin "10") (pinfunction "10_10") (pintype "passive"))
      (node (ref "J13") (pin "2") (pinfunction "2_2") (pintype "passive"))
      (node (ref "U15") (pin "2") (pinfunction "VCC_2") (pintype "passive"))
    )
    (net (code "15") (name "GNSS2_P5V0") (class "Default")
      (node (ref "C35") (pin "1") (pinfunction "1_1") (pintype "passive"))
      (node (ref "C37") (pin "2") (pinfunction "2_2") (pintype "passive"))
      (node (ref "C56") (pin "1") (pinfunction "1_1") (pintype "passive"))
      (node (ref "C64") (pin "2") (pinfunction "2_2") (pintype "passive"))
      (node (ref "J13") (pin "1") (pinfunction "1_1") (pintype "passive"))
      (node (ref "J13") (pin "9") (pinfunction "9_9") (pintype "passive"))
      (node (ref "U15") (pin "1") (pinfunction "VCC_ANT_1") (pintype "passive"))
    )
    (net (code "16") (name "GPS1_PIN13") (class "Default")
      (node (ref "J6") (pin "13") (pinfunction "13_13") (pintype "passive"))
    )
    (net (code "17") (name "GPS1_PIN14") (class "Default")
      (node (ref "J6") (pin "14") (pinfunction "14_14") (pintype "passive"))
    )
    (net (code "18") (name "GPS1_PIN15") (class "Default")
      (node (ref "J6") (pin "15") (pinfunction "15_15") (pintype "passive"))
    )
    (net (code "19") (name "GPS1_RST") (class "Default")
      (node (ref "J6") (pin "4") (pinfunction "4_4") (pintype "passive"))
      (node (ref "U9") (pin "4") (pinfunction "RST_4") (pintype "passive"))
    )
    (net (code "20") (name "GPS2_PIN13") (class "Default")
      (node (ref "J13") (pin "13") (pinfunction "13_13") (pintype "passive"))
    )
    (net (code "21") (name "GPS2_PIN14") (class "Default")
      (node (ref "J13") (pin "14") (pinfunction "14_14") (pintype "passive"))
    )
    (net (code "22") (name "GPS2_PIN15") (class "Default")
      (node (ref "J13") (pin "15") (pinfunction "15_15") (pintype "passive"))
    )
    (net (code "23") (name "GPS2_RST") (class "Default")
      (node (ref "J13") (pin "4") (pinfunction "4_4") (pintype "passive"))
      (node (ref "U15") (pin "4") (pinfunction "RST_4") (pintype "passive"))
    )
    (net (code "24") (name "MAC_FREQ_CTRL") (class "Default")
      (node (ref "R186") (pin "2") (pinfunction "2_2") (pintype "passive"))
      (node (ref "R48") (pin "2") (pinfunction "2_2") (pintype "passive"))
    )
    (net (code "25") (name "Net-(P1-Pad1)") (class "Default")
      (node (ref "P1") (pin "1") (pinfunction "1_1") (pintype "passive"))
      (node (ref "R186") (pin "1") (pinfunction "1_1") (pintype "passive"))
    )
    (net (code "26") (name "Net-(P1-Pad5)") (class "Default")
      (node (ref "P1") (pin "5") (pinfunction "5_5") (pintype "passive"))
      (node (ref "R48") (pin "1") (pinfunction "1_1") (pintype "passive"))
    )
    (net (code "27") (name "Net-(U13-BL_IND)") (class "Default")
      (node (ref "R55") (pin "2") (pinfunction "2_2") (pintype "passive"))
      (node (ref "U13") (pin "10") (pinfunction "BL_IND_10") (pintype "output"))
    )
    (net (code "28") (name "Net-(U13-CAP)") (class "Default")
      (node (ref "C65") (pin "1") (pinfunction "1_1") (pintype "passive"))
      (node (ref "U13") (pin "9") (pinfunction "CAP_9") (pintype "passive"))
    )
    (net (code "29") (name "Net-(U13-COM3)") (class "Default")
      (node (ref "R53") (pin "1") (pinfunction "1_1") (pintype "passive"))
      (node (ref "R56") (pin "2") (pinfunction "2_2") (pintype "passive"))
      (node (ref "U13") (pin "17") (pinfunction "COM3_17") (pintype "input"))
    )
    (net (code "30") (name "Net-(U13-SWCLK)") (class "Default")
      (node (ref "R58") (pin "2") (pinfunction "2_2") (pintype "passive"))
      (node (ref "U13") (pin "8") (pinfunction "SWCLK_8") (pintype "input"))
    )
    (net (code "31") (name "Net-(U13-SWDIO)") (class "Default")
      (node (ref "R57") (pin "2") (pinfunction "2_2") (pintype "passive"))
      (node (ref "U13") (pin "7") (pinfunction "SWDIO_7") (pintype "bidirectional"))
    )
    (net (code "32") (name "Net-(U13-~{BOOT_LOAD_PIN})") (class "Default")
      (node (ref "R51") (pin "2") (pinfunction "2_2") (pintype "passive"))
      (node (ref "U13") (pin "4") (pinfunction "~{BOOT_LOAD_PIN}_4") (pintype "input"))
    )
    (net (code "33") (name "Net-(U13-~{RESET})") (class "Default")
      (node (ref "R52") (pin "1") (pinfunction "1_1") (pintype "passive"))
      (node (ref "R54") (pin "2") (pinfunction "2_2") (pintype "passive"))
      (node (ref "U13") (pin "11") (pinfunction "~{RESET}_11") (pintype "input"))
    )
    (net (code "34") (name "PCIE_PERST") (class "Default")
      (node (ref "R54") (pin "1") (pinfunction "1_1") (pintype "passive"))
    )
    (net (code "35") (name "RCB_GPS1_PIN11") (class "Default")
      (node (ref "J6") (pin "11") (pinfunction "11_11") (pintype "passive"))
    )
    (net (code "36") (name "RCB_GPS1_PIN12") (class "Default")
      (node (ref "J6") (pin "12") (pinfunction "12_12") (pintype "passive"))
    )
    (net (code "37") (name "RCB_GPS1_RX") (class "Default")
      (node (ref "J6") (pin "5") (pinfunction "5_5") (pintype "passive"))
      (node (ref "U9") (pin "5") (pinfunction "RXD_5") (pintype "passive"))
    )
    (net (code "38") (name "RCB_GPS1_TP1") (class "Default")
      (node (ref "J6") (pin "6") (pinfunction "6_6") (pintype "passive"))
      (node (ref "U9") (pin "6") (pinfunction "TP1_6") (pintype "passive"))
    )
    (net (code "39") (name "RCB_GPS1_TP2") (class "Default")
      (node (ref "J6") (pin "7") (pinfunction "7_7") (pintype "passive"))
      (node (ref "U9") (pin "7") (pinfunction "TP2_7") (pintype "passive"))
    )
    (net (code "40") (name "RCB_GPS1_TX") (class "Default")
      (node (ref "J6") (pin "3") (pinfunction "3_3") (pintype "passive"))
      (node (ref "U9") (pin "3") (pinfunction "TXD_3") (pintype "passive"))
    )
    (net (code "41") (name "RCB_GPS2_PIN11") (class "Default")
      (node (ref "J13") (pin "11") (pinfunction "11_11") (pintype "passive"))
    )
    (net (code "42") (name "RCB_GPS2_PIN12") (class "Default")
      (node (ref "J13") (pin "12") (pinfunction "12_12") (pintype "passive"))
    )
    (net (code "43") (name "RCB_GPS2_RX") (class "Default")
      (node (ref "J13") (pin "5") (pinfunction "5_5") (pintype "passive"))
      (node (ref "U15") (pin "5") (pinfunction "RXD_5") (pintype "passive"))
    )
    (net (code "44") (name "RCB_GPS2_TP1") (class "Default")
      (node (ref "J13") (pin "6") (pinfunction "6_6") (pintype "passive"))
      (node (ref "U15") (pin "6") (pinfunction "TP1_6") (pintype "passive"))
    )
    (net (code "45") (name "RCB_GPS2_TP2") (class "Default")
      (node (ref "J13") (pin "7") (pinfunction "7_7") (pintype "passive"))
      (node (ref "U15") (pin "7") (pinfunction "TP2_7") (pintype "passive"))
    )
    (net (code "46") (name "RCB_GPS2_TX") (class "Default")
      (node (ref "J13") (pin "3") (pinfunction "3_3") (pintype "passive"))
      (node (ref "U15") (pin "3") (pinfunction "TXD_3") (pintype "passive"))
    )
    (net (code "47") (name "SCL") (class "Default")
      (node (ref "U7") (pin "1") (pinfunction "SCL_1") (pintype "input"))
    )
    (net (code "48") (name "SDA") (class "Default")
      (node (ref "U7") (pin "3") (pinfunction "SDA_3") (pintype "bidirectional"))
    )
    (net (code "49") (name "SENS_I2C_SCL") (class "Default")
      (node (ref "U13") (pin "19") (pinfunction "COM1_19") (pintype "bidirectional"))
      (node (ref "U14") (pin "4") (pinfunction "SCK_4") (pintype "input"))
    )
    (net (code "50") (name "SENS_I2C_SDA") (class "Default")
      (node (ref "U13") (pin "20") (pinfunction "COM0_20") (pintype "bidirectional"))
      (node (ref "U14") (pin "3") (pinfunction "SDI_3") (pintype "bidirectional"))
    )
    (net (code "51") (name "unconnected-(U13-NC-Pad1)") (class "Default")
      (node (ref "U13") (pin "1") (pinfunction "NC_1") (pintype "passive"))
    )
    (net (code "52") (name "unconnected-(U13-NC-Pad12)") (class "Default")
      (node (ref "U13") (pin "12") (pinfunction "NC_12") (pintype "passive"))
    )
    (net (code "53") (name "unconnected-(U13-NC-Pad13)") (class "Default")
      (node (ref "U13") (pin "13") (pinfunction "NC_13") (pintype "passive"))
    )
    (net (code "54") (name "unconnected-(U13-NC-Pad15)") (class "Default")
      (node (ref "U13") (pin "15") (pinfunction "NC_15") (pintype "passive"))
    )
    (net (code "55") (name "unconnected-(U13-NC-Pad16)") (class "Default")
      (node (ref "U13") (pin "16") (pinfunction "NC_16") (pintype "passive"))
    )
    (net (code "56") (name "unconnected-(U13-NC-Pad21)") (class "Default")
      (node (ref "U13") (pin "21") (pinfunction "NC_21") (pintype "passive"))
    )
    (net (code "57") (name "unconnected-(U13-NC-Pad22)") (class "Default")
      (node (ref "U13") (pin "22") (pinfunction "NC_22") (pintype "passive"))
    )
    (net (code "58") (name "unconnected-(U13-NC-Pad23)") (class "Default")
      (node (ref "U13") (pin "23") (pinfunction "NC_23") (pintype "passive"))
    )
    (net (code "59") (name "unconnected-(U13-NC-Pad24)") (class "Default")
      (node (ref "U13") (pin "24") (pinfunction "NC_24") (pintype "passive"))
    )
    (net (code "60") (name "unconnected-(U25-NC-Pad5)") (class "Default")
      (node (ref "U25") (pin "5") (pinfunction "NC_5") (pintype "passive"))
    )
  )
)
